# controller.net
KiCad netlist of a schematic drawn in EAGLE
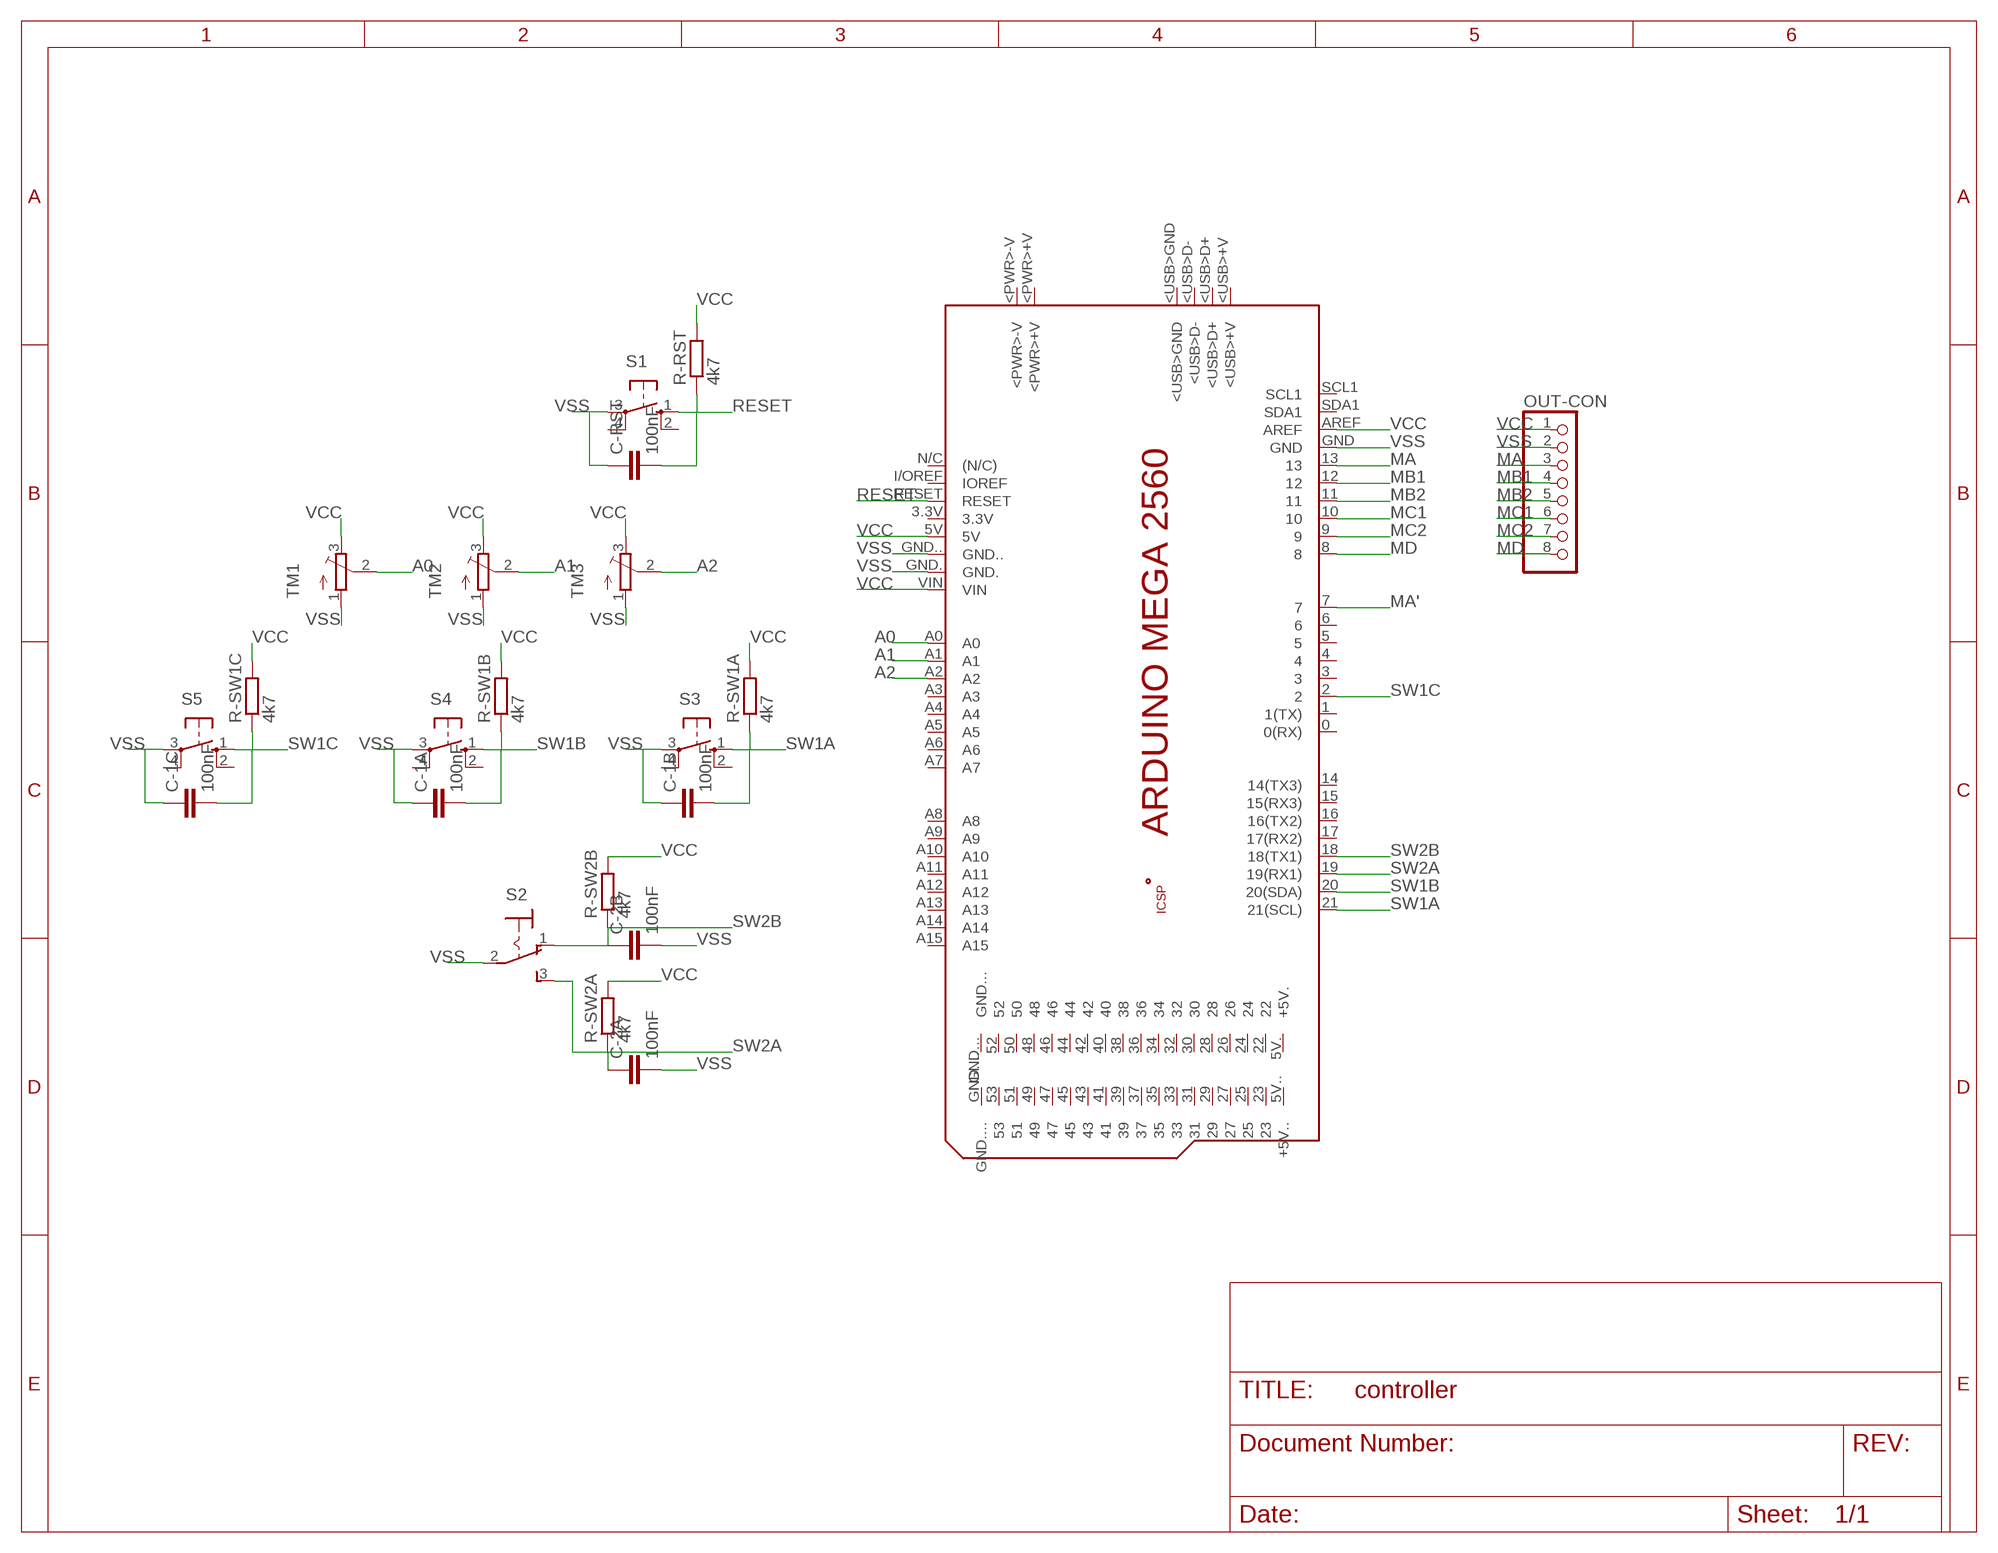
[diagram p0: schematic, sheet 1]

(export (version "E")
  (design (tool "Eeschema 10.0.6"))
  (components
    (comp (ref "C-1A")
      (value "100nF")
      (footprint "eagle-import:C025-024X044")
      (libsource (lib "eagle-import") (part "C-EU025-024X044"))
    )
    (comp (ref "C-1B")
      (value "100nF")
      (footprint "eagle-import:C025-024X044")
      (libsource (lib "eagle-import") (part "C-EU025-024X044"))
    )
    (comp (ref "C-1C")
      (value "100nF")
      (footprint "eagle-import:C025-024X044")
      (libsource (lib "eagle-import") (part "C-EU025-024X044"))
    )
    (comp (ref "C-2A")
      (value "100nF")
      (footprint "eagle-import:C025-024X044")
      (libsource (lib "eagle-import") (part "C-EU025-024X044"))
    )
    (comp (ref "C-2B")
      (value "100nF")
      (footprint "eagle-import:C025-024X044")
      (libsource (lib "eagle-import") (part "C-EU025-024X044"))
    )
    (comp (ref "C-RST")
      (value "100nF")
      (footprint "eagle-import:C025-024X044")
      (libsource (lib "eagle-import") (part "C-EU025-024X044"))
    )
    (comp (ref "OUT-CON")
      (value "PINHD-1X8")
      (footprint "eagle-import:1X08")
      (libsource (lib "eagle-import") (part "PINHD-1X8"))
    )
    (comp (ref "PCB1")
      (value "ARDUINO_MEGA2560")
      (footprint "eagle-import:ARDUINO_MEGA2560")
      (libsource (lib "eagle-import") (part "ARDUINO_MEGA2560"))
    )
    (comp (ref "R-RST")
      (value "4k7")
      (footprint "eagle-import:0204_7")
      (libsource (lib "eagle-import") (part "R-EU_0204/7"))
    )
    (comp (ref "R-SW1A")
      (value "4k7")
      (footprint "eagle-import:0204_7")
      (libsource (lib "eagle-import") (part "R-EU_0204/7"))
    )
    (comp (ref "R-SW1B")
      (value "4k7")
      (footprint "eagle-import:0204_7")
      (libsource (lib "eagle-import") (part "R-EU_0204/7"))
    )
    (comp (ref "R-SW1C")
      (value "4k7")
      (footprint "eagle-import:0204_7")
      (libsource (lib "eagle-import") (part "R-EU_0204/7"))
    )
    (comp (ref "R-SW2A")
      (value "4k7")
      (footprint "eagle-import:0204_7")
      (libsource (lib "eagle-import") (part "R-EU_0204/7"))
    )
    (comp (ref "R-SW2B")
      (value "4k7")
      (footprint "eagle-import:0204_7")
      (libsource (lib "eagle-import") (part "R-EU_0204/7"))
    )
    (comp (ref "S1")
      (value "10-XX")
      (footprint "eagle-import:B3F-10XX")
      (fields (field (name "MPN") "B3F-1000"))
      (libsource (lib "eagle-import") (part "10-XX"))
    )
    (comp (ref "S2")
      (value "M9040P")
      (footprint "eagle-import:M9040P")
      (libsource (lib "eagle-import") (part "M9040P"))
    )
    (comp (ref "S3")
      (value "10-XX")
      (footprint "eagle-import:B3F-10XX")
      (fields (field (name "MPN") "B3F-1000"))
      (libsource (lib "eagle-import") (part "10-XX"))
    )
    (comp (ref "S4")
      (value "10-XX")
      (footprint "eagle-import:B3F-10XX")
      (fields (field (name "MPN") "B3F-1000"))
      (libsource (lib "eagle-import") (part "10-XX"))
    )
    (comp (ref "S5")
      (value "10-XX")
      (footprint "eagle-import:B3F-10XX")
      (fields (field (name "MPN") "B3F-1000"))
      (libsource (lib "eagle-import") (part "10-XX"))
    )
    (comp (ref "TM1")
      (value "TRIMPOT3386")
      (footprint "eagle-import:TRIM-3386")
      (libsource (lib "eagle-import") (part "TRIMPOT3386"))
    )
    (comp (ref "TM2")
      (value "TRIMPOT3386")
      (footprint "eagle-import:TRIM-3386")
      (libsource (lib "eagle-import") (part "TRIMPOT3386"))
    )
    (comp (ref "TM3")
      (value "TRIMPOT3386")
      (footprint "eagle-import:TRIM-3386")
      (libsource (lib "eagle-import") (part "TRIMPOT3386"))
    )
  )
  (nets
    (net (code "1") (name "/A0") (class "Default")
      (node (ref "PCB1") (pin "A0") (pinfunction "A0_A0") (pintype "bidirectional"))
      (node (ref "TM1") (pin "2") (pinfunction "S_2") (pintype "passive"))
    )
    (net (code "2") (name "/A1") (class "Default")
      (node (ref "PCB1") (pin "A1") (pinfunction "A1_A1") (pintype "bidirectional"))
      (node (ref "TM2") (pin "2") (pinfunction "S_2") (pintype "passive"))
    )
    (net (code "3") (name "/A2") (class "Default")
      (node (ref "PCB1") (pin "A2") (pinfunction "A2_A2") (pintype "bidirectional"))
      (node (ref "TM3") (pin "2") (pinfunction "S_2") (pintype "passive"))
    )
    (net (code "4") (name "/MA") (class "Default")
      (node (ref "OUT-CON") (pin "3") (pinfunction "3_3") (pintype "passive"))
      (node (ref "PCB1") (pin "13") (pinfunction "13_13") (pintype "bidirectional"))
    )
    (net (code "5") (name "/MA'") (class "Default")
      (node (ref "PCB1") (pin "7") (pinfunction "7_7") (pintype "bidirectional"))
    )
    (net (code "6") (name "/MB1") (class "Default")
      (node (ref "OUT-CON") (pin "4") (pinfunction "4_4") (pintype "passive"))
      (node (ref "PCB1") (pin "12") (pinfunction "12_12") (pintype "bidirectional"))
    )
    (net (code "7") (name "/MB2") (class "Default")
      (node (ref "OUT-CON") (pin "5") (pinfunction "5_5") (pintype "passive"))
      (node (ref "PCB1") (pin "11") (pinfunction "11_11") (pintype "bidirectional"))
    )
    (net (code "8") (name "/MC1") (class "Default")
      (node (ref "OUT-CON") (pin "6") (pinfunction "6_6") (pintype "passive"))
      (node (ref "PCB1") (pin "10") (pinfunction "10_10") (pintype "bidirectional"))
    )
    (net (code "9") (name "/MC2") (class "Default")
      (node (ref "OUT-CON") (pin "7") (pinfunction "7_7") (pintype "passive"))
      (node (ref "PCB1") (pin "9") (pinfunction "9_9") (pintype "bidirectional"))
    )
    (net (code "10") (name "/MD") (class "Default")
      (node (ref "OUT-CON") (pin "8") (pinfunction "8_8") (pintype "passive"))
      (node (ref "PCB1") (pin "8") (pinfunction "8_8") (pintype "bidirectional"))
    )
    (net (code "11") (name "/RESET") (class "Default")
      (node (ref "C-RST") (pin "2") (pinfunction "2_2") (pintype "passive"))
      (node (ref "PCB1") (pin "RESET") (pinfunction "RESET_RESET") (pintype "bidirectional"))
      (node (ref "R-RST") (pin "1") (pinfunction "1_1") (pintype "passive"))
      (node (ref "S1") (pin "1") (pinfunction "S_1") (pintype "passive"))
    )
    (net (code "12") (name "/SW1A") (class "Default")
      (node (ref "C-1B") (pin "2") (pinfunction "2_2") (pintype "passive"))
      (node (ref "PCB1") (pin "21") (pinfunction "21(SCL)_21") (pintype "bidirectional"))
      (node (ref "R-SW1A") (pin "1") (pinfunction "1_1") (pintype "passive"))
      (node (ref "S3") (pin "1") (pinfunction "S_1") (pintype "passive"))
    )
    (net (code "13") (name "/SW1B") (class "Default")
      (node (ref "C-1A") (pin "2") (pinfunction "2_2") (pintype "passive"))
      (node (ref "PCB1") (pin "20") (pinfunction "20(SDA)_20") (pintype "bidirectional"))
      (node (ref "R-SW1B") (pin "1") (pinfunction "1_1") (pintype "passive"))
      (node (ref "S4") (pin "1") (pinfunction "S_1") (pintype "passive"))
    )
    (net (code "14") (name "/SW1C") (class "Default")
      (node (ref "C-1C") (pin "2") (pinfunction "2_2") (pintype "passive"))
      (node (ref "PCB1") (pin "2") (pinfunction "2_2") (pintype "bidirectional"))
      (node (ref "R-SW1C") (pin "1") (pinfunction "1_1") (pintype "passive"))
      (node (ref "S5") (pin "1") (pinfunction "S_1") (pintype "passive"))
    )
    (net (code "15") (name "/SW2A") (class "Default")
      (node (ref "C-2A") (pin "1") (pinfunction "1_1") (pintype "passive"))
      (node (ref "PCB1") (pin "19") (pinfunction "19(RX1)_19") (pintype "bidirectional"))
      (node (ref "R-SW2A") (pin "1") (pinfunction "1_1") (pintype "passive"))
      (node (ref "S2") (pin "3") (pinfunction "S_3") (pintype "passive"))
    )
    (net (code "16") (name "/SW2B") (class "Default")
      (node (ref "C-2B") (pin "1") (pinfunction "1_1") (pintype "passive"))
      (node (ref "PCB1") (pin "18") (pinfunction "18(TX1)_18") (pintype "bidirectional"))
      (node (ref "R-SW2B") (pin "1") (pinfunction "1_1") (pintype "passive"))
      (node (ref "S2") (pin "1") (pinfunction "O_1") (pintype "passive"))
    )
    (net (code "17") (name "/VCC") (class "Default")
      (node (ref "OUT-CON") (pin "1") (pinfunction "1_1") (pintype "passive"))
      (node (ref "PCB1") (pin "5V") (pinfunction "5V_5V") (pintype "bidirectional"))
      (node (ref "PCB1") (pin "AREF") (pinfunction "AREF_AREF") (pintype "bidirectional"))
      (node (ref "PCB1") (pin "VIN") (pinfunction "VIN_VIN") (pintype "bidirectional"))
      (node (ref "R-RST") (pin "2") (pinfunction "2_2") (pintype "passive"))
      (node (ref "R-SW1A") (pin "2") (pinfunction "2_2") (pintype "passive"))
      (node (ref "R-SW1B") (pin "2") (pinfunction "2_2") (pintype "passive"))
      (node (ref "R-SW1C") (pin "2") (pinfunction "2_2") (pintype "passive"))
      (node (ref "R-SW2A") (pin "2") (pinfunction "2_2") (pintype "passive"))
      (node (ref "R-SW2B") (pin "2") (pinfunction "2_2") (pintype "passive"))
      (node (ref "TM1") (pin "3") (pinfunction "E_3") (pintype "passive"))
      (node (ref "TM2") (pin "3") (pinfunction "E_3") (pintype "passive"))
      (node (ref "TM3") (pin "3") (pinfunction "E_3") (pintype "passive"))
    )
    (net (code "18") (name "/VSS") (class "Default")
      (node (ref "C-1A") (pin "1") (pinfunction "1_1") (pintype "passive"))
      (node (ref "C-1B") (pin "1") (pinfunction "1_1") (pintype "passive"))
      (node (ref "C-1C") (pin "1") (pinfunction "1_1") (pintype "passive"))
      (node (ref "C-2A") (pin "2") (pinfunction "2_2") (pintype "passive"))
      (node (ref "C-2B") (pin "2") (pinfunction "2_2") (pintype "passive"))
      (node (ref "C-RST") (pin "1") (pinfunction "1_1") (pintype "passive"))
      (node (ref "OUT-CON") (pin "2") (pinfunction "2_2") (pintype "passive"))
      (node (ref "PCB1") (pin "GND") (pinfunction "GND_GND") (pintype "bidirectional"))
      (node (ref "PCB1") (pin "GND.") (pinfunction "GND._GND.") (pintype "bidirectional"))
      (node (ref "PCB1") (pin "GND..") (pinfunction "GND.._GND..") (pintype "bidirectional"))
      (node (ref "S1") (pin "3") (pinfunction "P_3") (pintype "passive"))
      (node (ref "S2") (pin "2") (pinfunction "P_2") (pintype "passive"))
      (node (ref "S3") (pin "3") (pinfunction "P_3") (pintype "passive"))
      (node (ref "S4") (pin "3") (pinfunction "P_3") (pintype "passive"))
      (node (ref "S5") (pin "3") (pinfunction "P_3") (pintype "passive"))
      (node (ref "TM1") (pin "1") (pinfunction "A_1") (pintype "passive"))
      (node (ref "TM2") (pin "1") (pinfunction "A_1") (pintype "passive"))
      (node (ref "TM3") (pin "1") (pinfunction "A_1") (pintype "passive"))
    )
    (net (code "19") (name "unconnected-(PCB1-(N{slash}C)-PadN{slash}C)") (class "Default")
      (node (ref "PCB1") (pin "N/C") (pinfunction "(N/C)_N/C") (pintype "bidirectional"))
    )
    (net (code "20") (name "unconnected-(PCB1-+5V.-Pad5V.)") (class "Default")
      (node (ref "PCB1") (pin "5V.") (pinfunction "+5V._5V.") (pintype "bidirectional"))
    )
    (net (code "21") (name "unconnected-(PCB1-+5V..-Pad5V..)") (class "Default")
      (node (ref "PCB1") (pin "5V..") (pinfunction "+5V.._5V..") (pintype "bidirectional"))
    )
    (net (code "22") (name "unconnected-(PCB1-0(RX)-Pad0)") (class "Default")
      (node (ref "PCB1") (pin "0") (pinfunction "0(RX)_0") (pintype "bidirectional"))
    )
    (net (code "23") (name "unconnected-(PCB1-1(TX)-Pad1)") (class "Default")
      (node (ref "PCB1") (pin "1") (pinfunction "1(TX)_1") (pintype "bidirectional"))
    )
    (net (code "24") (name "unconnected-(PCB1-14(TX3)-Pad14)") (class "Default")
      (node (ref "PCB1") (pin "14") (pinfunction "14(TX3)_14") (pintype "bidirectional"))
    )
    (net (code "25") (name "unconnected-(PCB1-15(RX3)-Pad15)") (class "Default")
      (node (ref "PCB1") (pin "15") (pinfunction "15(RX3)_15") (pintype "bidirectional"))
    )
    (net (code "26") (name "unconnected-(PCB1-16(TX2)-Pad16)") (class "Default")
      (node (ref "PCB1") (pin "16") (pinfunction "16(TX2)_16") (pintype "bidirectional"))
    )
    (net (code "27") (name "unconnected-(PCB1-17(RX2)-Pad17)") (class "Default")
      (node (ref "PCB1") (pin "17") (pinfunction "17(RX2)_17") (pintype "bidirectional"))
    )
    (net (code "28") (name "unconnected-(PCB1-IOREF-PadI{slash}OREF)") (class "Default")
      (node (ref "PCB1") (pin "I/OREF") (pinfunction "IOREF_I/OREF") (pintype "bidirectional"))
    )
    (net (code "29") (name "unconnected-(PCB1-Pad+5V_)") (class "Default")
      (node (ref "PCB1") (pin "+5V_") (pinfunction "+5V__+5V_") (pintype "bidirectional"))
    )
    (net (code "30") (name "unconnected-(PCB1-Pad3)") (class "Default")
      (node (ref "PCB1") (pin "3") (pinfunction "3_3") (pintype "bidirectional"))
    )
    (net (code "31") (name "unconnected-(PCB1-Pad3.3V)") (class "Default")
      (node (ref "PCB1") (pin "3.3V") (pinfunction "3.3V_3.3V") (pintype "bidirectional"))
    )
    (net (code "32") (name "unconnected-(PCB1-Pad4)") (class "Default")
      (node (ref "PCB1") (pin "4") (pinfunction "4_4") (pintype "bidirectional"))
    )
    (net (code "33") (name "unconnected-(PCB1-Pad5)") (class "Default")
      (node (ref "PCB1") (pin "5") (pinfunction "5_5") (pintype "bidirectional"))
    )
    (net (code "34") (name "unconnected-(PCB1-Pad6)") (class "Default")
      (node (ref "PCB1") (pin "6") (pinfunction "6_6") (pintype "bidirectional"))
    )
    (net (code "35") (name "unconnected-(PCB1-Pad22)") (class "Default")
      (node (ref "PCB1") (pin "22") (pinfunction "22_22") (pintype "bidirectional"))
    )
    (net (code "36") (name "unconnected-(PCB1-Pad23)") (class "Default")
      (node (ref "PCB1") (pin "23") (pinfunction "23_23") (pintype "bidirectional"))
    )
    (net (code "37") (name "unconnected-(PCB1-Pad24)") (class "Default")
      (node (ref "PCB1") (pin "24") (pinfunction "24_24") (pintype "bidirectional"))
    )
    (net (code "38") (name "unconnected-(PCB1-Pad25)") (class "Default")
      (node (ref "PCB1") (pin "25") (pinfunction "25_25") (pintype "bidirectional"))
    )
    (net (code "39") (name "unconnected-(PCB1-Pad26)") (class "Default")
      (node (ref "PCB1") (pin "26") (pinfunction "26_26") (pintype "bidirectional"))
    )
    (net (code "40") (name "unconnected-(PCB1-Pad27)") (class "Default")
      (node (ref "PCB1") (pin "27") (pinfunction "27_27") (pintype "bidirectional"))
    )
    (net (code "41") (name "unconnected-(PCB1-Pad28)") (class "Default")
      (node (ref "PCB1") (pin "28") (pinfunction "28_28") (pintype "bidirectional"))
    )
    (net (code "42") (name "unconnected-(PCB1-Pad29)") (class "Default")
      (node (ref "PCB1") (pin "29") (pinfunction "29_29") (pintype "bidirectional"))
    )
    (net (code "43") (name "unconnected-(PCB1-Pad30)") (class "Default")
      (node (ref "PCB1") (pin "30") (pinfunction "30_30") (pintype "bidirectional"))
    )
    (net (code "44") (name "unconnected-(PCB1-Pad31)") (class "Default")
      (node (ref "PCB1") (pin "31") (pinfunction "31_31") (pintype "bidirectional"))
    )
    (net (code "45") (name "unconnected-(PCB1-Pad32)") (class "Default")
      (node (ref "PCB1") (pin "32") (pinfunction "32_32") (pintype "bidirectional"))
    )
    (net (code "46") (name "unconnected-(PCB1-Pad33)") (class "Default")
      (node (ref "PCB1") (pin "33") (pinfunction "33_33") (pintype "bidirectional"))
    )
    (net (code "47") (name "unconnected-(PCB1-Pad34)") (class "Default")
      (node (ref "PCB1") (pin "34") (pinfunction "34_34") (pintype "bidirectional"))
    )
    (net (code "48") (name "unconnected-(PCB1-Pad35)") (class "Default")
      (node (ref "PCB1") (pin "35") (pinfunction "35_35") (pintype "bidirectional"))
    )
    (net (code "49") (name "unconnected-(PCB1-Pad36)") (class "Default")
      (node (ref "PCB1") (pin "36") (pinfunction "36_36") (pintype "bidirectional"))
    )
    (net (code "50") (name "unconnected-(PCB1-Pad37)") (class "Default")
      (node (ref "PCB1") (pin "37") (pinfunction "37_37") (pintype "bidirectional"))
    )
    (net (code "51") (name "unconnected-(PCB1-Pad38)") (class "Default")
      (node (ref "PCB1") (pin "38") (pinfunction "38_38") (pintype "bidirectional"))
    )
    (net (code "52") (name "unconnected-(PCB1-Pad39)") (class "Default")
      (node (ref "PCB1") (pin "39") (pinfunction "39_39") (pintype "bidirectional"))
    )
    (net (code "53") (name "unconnected-(PCB1-Pad40)") (class "Default")
      (node (ref "PCB1") (pin "40") (pinfunction "40_40") (pintype "bidirectional"))
    )
    (net (code "54") (name "unconnected-(PCB1-Pad41)") (class "Default")
      (node (ref "PCB1") (pin "41") (pinfunction "41_41") (pintype "bidirectional"))
    )
    (net (code "55") (name "unconnected-(PCB1-Pad42)") (class "Default")
      (node (ref "PCB1") (pin "42") (pinfunction "42_42") (pintype "bidirectional"))
    )
    (net (code "56") (name "unconnected-(PCB1-Pad43)") (class "Default")
      (node (ref "PCB1") (pin "43") (pinfunction "43_43") (pintype "bidirectional"))
    )
    (net (code "57") (name "unconnected-(PCB1-Pad44)") (class "Default")
      (node (ref "PCB1") (pin "44") (pinfunction "44_44") (pintype "bidirectional"))
    )
    (net (code "58") (name "unconnected-(PCB1-Pad45)") (class "Default")
      (node (ref "PCB1") (pin "45") (pinfunction "45_45") (pintype "bidirectional"))
    )
    (net (code "59") (name "unconnected-(PCB1-Pad46)") (class "Default")
      (node (ref "PCB1") (pin "46") (pinfunction "46_46") (pintype "bidirectional"))
    )
    (net (code "60") (name "unconnected-(PCB1-Pad47)") (class "Default")
      (node (ref "PCB1") (pin "47") (pinfunction "47_47") (pintype "bidirectional"))
    )
    (net (code "61") (name "unconnected-(PCB1-Pad48)") (class "Default")
      (node (ref "PCB1") (pin "48") (pinfunction "48_48") (pintype "bidirectional"))
    )
    (net (code "62") (name "unconnected-(PCB1-Pad49)") (class "Default")
      (node (ref "PCB1") (pin "49") (pinfunction "49_49") (pintype "bidirectional"))
    )
    (net (code "63") (name "unconnected-(PCB1-Pad50)") (class "Default")
      (node (ref "PCB1") (pin "50") (pinfunction "50_50") (pintype "bidirectional"))
    )
    (net (code "64") (name "unconnected-(PCB1-Pad51)") (class "Default")
      (node (ref "PCB1") (pin "51") (pinfunction "51_51") (pintype "bidirectional"))
    )
    (net (code "65") (name "unconnected-(PCB1-Pad52)") (class "Default")
      (node (ref "PCB1") (pin "52") (pinfunction "52_52") (pintype "bidirectional"))
    )
    (net (code "66") (name "unconnected-(PCB1-Pad53)") (class "Default")
      (node (ref "PCB1") (pin "53") (pinfunction "53_53") (pintype "bidirectional"))
    )
    (net (code "67") (name "unconnected-(PCB1-Pad<PWR>+V)") (class "Default")
      (node (ref "PCB1") (pin "<PWR>+V") (pinfunction "<PWR>+V_<PWR>+V") (pintype "no_connect"))
    )
    (net (code "68") (name "unconnected-(PCB1-Pad<PWR>-V)") (class "Default")
      (node (ref "PCB1") (pin "<PWR>-V") (pinfunction "<PWR>-V_<PWR>-V") (pintype "no_connect"))
    )
    (net (code "69") (name "unconnected-(PCB1-Pad<USB>+V)") (class "Default")
      (node (ref "PCB1") (pin "<USB>+V") (pinfunction "<USB>+V_<USB>+V") (pintype "no_connect"))
    )
    (net (code "70") (name "unconnected-(PCB1-Pad<USB>D+)") (class "Default")
      (node (ref "PCB1") (pin "<USB>D+") (pinfunction "<USB>D+_<USB>D+") (pintype "no_connect"))
    )
    (net (code "71") (name "unconnected-(PCB1-Pad<USB>D-)") (class "Default")
      (node (ref "PCB1") (pin "<USB>D-") (pinfunction "<USB>D-_<USB>D-") (pintype "no_connect"))
    )
    (net (code "72") (name "unconnected-(PCB1-Pad<USB>GND)") (class "Default")
      (node (ref "PCB1") (pin "<USB>GND") (pinfunction "<USB>GND_<USB>GND") (pintype "no_connect"))
    )
    (net (code "73") (name "unconnected-(PCB1-PadA3)") (class "Default")
      (node (ref "PCB1") (pin "A3") (pinfunction "A3_A3") (pintype "bidirectional"))
    )
    (net (code "74") (name "unconnected-(PCB1-PadA4)") (class "Default")
      (node (ref "PCB1") (pin "A4") (pinfunction "A4_A4") (pintype "bidirectional"))
    )
    (net (code "75") (name "unconnected-(PCB1-PadA5)") (class "Default")
      (node (ref "PCB1") (pin "A5") (pinfunction "A5_A5") (pintype "bidirectional"))
    )
    (net (code "76") (name "unconnected-(PCB1-PadA6)") (class "Default")
      (node (ref "PCB1") (pin "A6") (pinfunction "A6_A6") (pintype "bidirectional"))
    )
    (net (code "77") (name "unconnected-(PCB1-PadA7)") (class "Default")
      (node (ref "PCB1") (pin "A7") (pinfunction "A7_A7") (pintype "bidirectional"))
    )
    (net (code "78") (name "unconnected-(PCB1-PadA8)") (class "Default")
      (node (ref "PCB1") (pin "A8") (pinfunction "A8_A8") (pintype "bidirectional"))
    )
    (net (code "79") (name "unconnected-(PCB1-PadA9)") (class "Default")
      (node (ref "PCB1") (pin "A9") (pinfunction "A9_A9") (pintype "bidirectional"))
    )
    (net (code "80") (name "unconnected-(PCB1-PadA10)") (class "Default")
      (node (ref "PCB1") (pin "A10") (pinfunction "A10_A10") (pintype "bidirectional"))
    )
    (net (code "81") (name "unconnected-(PCB1-PadA11)") (class "Default")
      (node (ref "PCB1") (pin "A11") (pinfunction "A11_A11") (pintype "bidirectional"))
    )
    (net (code "82") (name "unconnected-(PCB1-PadA12)") (class "Default")
      (node (ref "PCB1") (pin "A12") (pinfunction "A12_A12") (pintype "bidirectional"))
    )
    (net (code "83") (name "unconnected-(PCB1-PadA13)") (class "Default")
      (node (ref "PCB1") (pin "A13") (pinfunction "A13_A13") (pintype "bidirectional"))
    )
    (net (code "84") (name "unconnected-(PCB1-PadA14)") (class "Default")
      (node (ref "PCB1") (pin "A14") (pinfunction "A14_A14") (pintype "bidirectional"))
    )
    (net (code "85") (name "unconnected-(PCB1-PadA15)") (class "Default")
      (node (ref "PCB1") (pin "A15") (pinfunction "A15_A15") (pintype "bidirectional"))
    )
    (net (code "86") (name "unconnected-(PCB1-PadGND...)") (class "Default")
      (node (ref "PCB1") (pin "GND...") (pinfunction "GND..._GND...") (pintype "bidirectional"))
    )
    (net (code "87") (name "unconnected-(PCB1-PadGND....)") (class "Default")
      (node (ref "PCB1") (pin "GND....") (pinfunction "GND...._GND....") (pintype "bidirectional"))
    )
    (net (code "88") (name "unconnected-(PCB1-PadGND__)") (class "Default")
      (node (ref "PCB1") (pin "GND__") (pinfunction "GND___GND__") (pintype "bidirectional"))
    )
    (net (code "89") (name "unconnected-(PCB1-PadMISO)") (class "Default")
      (node (ref "PCB1") (pin "MISO") (pinfunction "MISO_MISO") (pintype "bidirectional"))
    )
    (net (code "90") (name "unconnected-(PCB1-PadMOSI)") (class "Default")
      (node (ref "PCB1") (pin "MOSI") (pinfunction "MOSI_MOSI") (pintype "bidirectional"))
    )
    (net (code "91") (name "unconnected-(PCB1-PadRESET.)") (class "Default")
      (node (ref "PCB1") (pin "RESET.") (pinfunction "RESET._RESET.") (pintype "bidirectional"))
    )
    (net (code "92") (name "unconnected-(PCB1-PadSCK)") (class "Default")
      (node (ref "PCB1") (pin "SCK") (pinfunction "SCK_SCK") (pintype "bidirectional"))
    )
    (net (code "93") (name "unconnected-(PCB1-PadSCL1)") (class "Default")
      (node (ref "PCB1") (pin "SCL1") (pinfunction "SCL1_SCL1") (pintype "bidirectional"))
    )
    (net (code "94") (name "unconnected-(PCB1-PadSDA1)") (class "Default")
      (node (ref "PCB1") (pin "SDA1") (pinfunction "SDA1_SDA1") (pintype "bidirectional"))
    )
    (net (code "95") (name "unconnected-(S1-P1-Pad4)") (class "Default")
      (node (ref "S1") (pin "4") (pinfunction "P1_4") (pintype "passive"))
    )
    (net (code "96") (name "unconnected-(S1-S1-Pad2)") (class "Default")
      (node (ref "S1") (pin "2") (pinfunction "S1_2") (pintype "passive"))
    )
    (net (code "97") (name "unconnected-(S3-P1-Pad4)") (class "Default")
      (node (ref "S3") (pin "4") (pinfunction "P1_4") (pintype "passive"))
    )
    (net (code "98") (name "unconnected-(S3-S1-Pad2)") (class "Default")
      (node (ref "S3") (pin "2") (pinfunction "S1_2") (pintype "passive"))
    )
    (net (code "99") (name "unconnected-(S4-P1-Pad4)") (class "Default")
      (node (ref "S4") (pin "4") (pinfunction "P1_4") (pintype "passive"))
    )
    (net (code "100") (name "unconnected-(S4-S1-Pad2)") (class "Default")
      (node (ref "S4") (pin "2") (pinfunction "S1_2") (pintype "passive"))
    )
    (net (code "101") (name "unconnected-(S5-P1-Pad4)") (class "Default")
      (node (ref "S5") (pin "4") (pinfunction "P1_4") (pintype "passive"))
    )
    (net (code "102") (name "unconnected-(S5-S1-Pad2)") (class "Default")
      (node (ref "S5") (pin "2") (pinfunction "S1_2") (pintype "passive"))
    )
  )
)
